# PIC18LF26K22.net
KiCad netlist of a schematic drawn in EAGLE
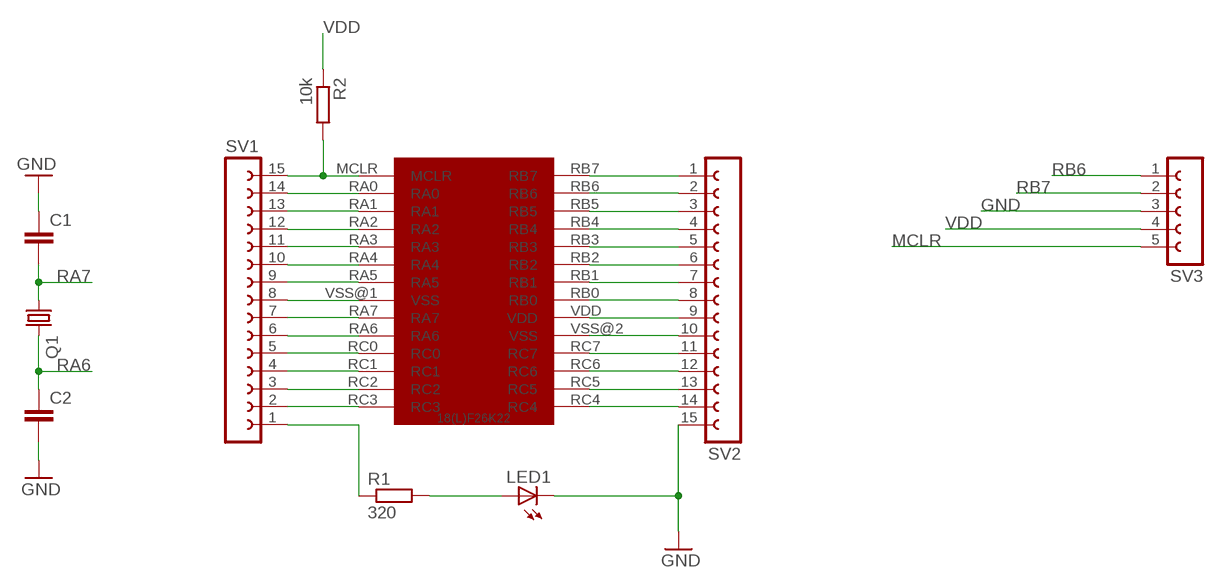
[diagram p0: schematic, sheet 1]

(export (version "E")
  (design (tool "Eeschema 10.0.6"))
  (components
    (comp (ref "C1")
      (value "C-EU025-024X044")
      (footprint "eagle-import:C025-024X044")
      (libsource (lib "eagle-import") (part "C-EU025-024X044"))
    )
    (comp (ref "C2")
      (value "C-EU025-024X044")
      (footprint "eagle-import:C025-024X044")
      (libsource (lib "eagle-import") (part "C-EU025-024X044"))
    )
    (comp (ref "LED1")
      (value "LED5MM")
      (footprint "eagle-import:LED5MM")
      (libsource (lib "eagle-import") (part "LED5MM"))
    )
    (comp (ref "Q1")
      (value "CRYSTALHC49S")
      (footprint "eagle-import:HC49_S")
      (libsource (lib "eagle-import") (part "CRYSTALHC49S"))
    )
    (comp (ref "R1")
      (value "320")
      (footprint "eagle-import:0207_10")
      (libsource (lib "eagle-import") (part "R-EU_0207/10"))
    )
    (comp (ref "R2")
      (value "10k")
      (footprint "eagle-import:0207_10")
      (libsource (lib "eagle-import") (part "R-EU_0207/10"))
    )
    (comp (ref "SV1")
      (value "FE15-1")
      (footprint "eagle-import:FE15")
      (libsource (lib "eagle-import") (part "FE15-1"))
    )
    (comp (ref "SV2")
      (value "FE15-1")
      (footprint "eagle-import:FE15")
      (libsource (lib "eagle-import") (part "FE15-1"))
    )
    (comp (ref "SV3")
      (value "FE05-1")
      (footprint "eagle-import:FE05-1")
      (libsource (lib "eagle-import") (part "FE05-1"))
    )
    (comp (ref "U$1")
      (value "PIC18(L)F26K22")
      (footprint "eagle-import:28-LEAD_SOIC")
      (libsource (lib "eagle-import") (part "PIC18(L)F26K22"))
    )
  )
  (nets
    (net (code "1") (name "/MCLR") (class "Default")
      (node (ref "R2") (pin "2") (pinfunction "2_2") (pintype "passive"))
      (node (ref "SV1") (pin "15") (pinfunction "15_15") (pintype "passive"))
      (node (ref "SV3") (pin "5") (pinfunction "5_5") (pintype "passive"))
      (node (ref "U$1") (pin "MCLR") (pinfunction "MCLR_MCLR") (pintype "bidirectional"))
    )
    (net (code "2") (name "/RA6") (class "Default")
      (node (ref "C2") (pin "1") (pinfunction "1_1") (pintype "passive"))
      (node (ref "Q1") (pin "2") (pinfunction "2_2") (pintype "passive"))
      (node (ref "SV1") (pin "6") (pinfunction "6_6") (pintype "passive"))
      (node (ref "U$1") (pin "RA6") (pinfunction "RA6_RA6") (pintype "bidirectional"))
    )
    (net (code "3") (name "/RA7") (class "Default")
      (node (ref "C1") (pin "2") (pinfunction "2_2") (pintype "passive"))
      (node (ref "Q1") (pin "1") (pinfunction "1_1") (pintype "passive"))
      (node (ref "SV1") (pin "7") (pinfunction "7_7") (pintype "passive"))
      (node (ref "U$1") (pin "RA7") (pinfunction "RA7_RA7") (pintype "bidirectional"))
    )
    (net (code "4") (name "/RB6") (class "Default")
      (node (ref "SV2") (pin "2") (pinfunction "2_2") (pintype "passive"))
      (node (ref "SV3") (pin "1") (pinfunction "1_1") (pintype "passive"))
      (node (ref "U$1") (pin "RB6") (pinfunction "RB6_RB6") (pintype "bidirectional"))
    )
    (net (code "5") (name "/RB7") (class "Default")
      (node (ref "SV2") (pin "1") (pinfunction "1_1") (pintype "passive"))
      (node (ref "SV3") (pin "2") (pinfunction "2_2") (pintype "passive"))
      (node (ref "U$1") (pin "RB7") (pinfunction "RB7_RB7") (pintype "bidirectional"))
    )
    (net (code "6") (name "/VDD") (class "Default")
      (node (ref "R2") (pin "1") (pinfunction "1_1") (pintype "passive"))
      (node (ref "SV2") (pin "9") (pinfunction "9_9") (pintype "passive"))
      (node (ref "SV3") (pin "4") (pinfunction "4_4") (pintype "passive"))
      (node (ref "U$1") (pin "VDD") (pinfunction "VDD_VDD") (pintype "bidirectional"))
    )
    (net (code "7") (name "GND") (class "Default")
      (node (ref "C1") (pin "1") (pinfunction "1_1") (pintype "passive"))
      (node (ref "C2") (pin "2") (pinfunction "2_2") (pintype "passive"))
      (node (ref "LED1") (pin "K") (pinfunction "C_K") (pintype "passive"))
      (node (ref "SV1") (pin "8") (pinfunction "8_8") (pintype "passive"))
      (node (ref "SV2") (pin "10") (pinfunction "10_10") (pintype "passive"))
      (node (ref "SV2") (pin "15") (pinfunction "15_15") (pintype "passive"))
      (node (ref "SV3") (pin "3") (pinfunction "3_3") (pintype "passive"))
      (node (ref "U$1") (pin "VSS@1") (pinfunction "VSS_VSS@1") (pintype "bidirectional"))
      (node (ref "U$1") (pin "VSS@2") (pinfunction "VSS_VSS@2") (pintype "bidirectional"))
    )
    (net (code "8") (name "Net-(LED1-PadA)") (class "Default")
      (node (ref "LED1") (pin "A") (pinfunction "A_A") (pintype "passive"))
      (node (ref "R1") (pin "2") (pinfunction "2_2") (pintype "passive"))
    )
    (net (code "9") (name "Net-(R1-Pad1)") (class "Default")
      (node (ref "R1") (pin "1") (pinfunction "1_1") (pintype "passive"))
      (node (ref "SV1") (pin "1") (pinfunction "1_1") (pintype "passive"))
    )
    (net (code "10") (name "Net-(SV1-Pad2)") (class "Default")
      (node (ref "SV1") (pin "2") (pinfunction "2_2") (pintype "passive"))
      (node (ref "U$1") (pin "RC3") (pinfunction "RC3_RC3") (pintype "bidirectional"))
    )
    (net (code "11") (name "Net-(SV1-Pad3)") (class "Default")
      (node (ref "SV1") (pin "3") (pinfunction "3_3") (pintype "passive"))
      (node (ref "U$1") (pin "RC2") (pinfunction "RC2_RC2") (pintype "bidirectional"))
    )
    (net (code "12") (name "Net-(SV1-Pad4)") (class "Default")
      (node (ref "SV1") (pin "4") (pinfunction "4_4") (pintype "passive"))
      (node (ref "U$1") (pin "RC1") (pinfunction "RC1_RC1") (pintype "bidirectional"))
    )
    (net (code "13") (name "Net-(SV1-Pad5)") (class "Default")
      (node (ref "SV1") (pin "5") (pinfunction "5_5") (pintype "passive"))
      (node (ref "U$1") (pin "RC0") (pinfunction "RC0_RC0") (pintype "bidirectional"))
    )
    (net (code "14") (name "Net-(SV1-Pad9)") (class "Default")
      (node (ref "SV1") (pin "9") (pinfunction "9_9") (pintype "passive"))
      (node (ref "U$1") (pin "RA5") (pinfunction "RA5_RA5") (pintype "bidirectional"))
    )
    (net (code "15") (name "Net-(SV1-Pad10)") (class "Default")
      (node (ref "SV1") (pin "10") (pinfunction "10_10") (pintype "passive"))
      (node (ref "U$1") (pin "RA4") (pinfunction "RA4_RA4") (pintype "bidirectional"))
    )
    (net (code "16") (name "Net-(SV1-Pad11)") (class "Default")
      (node (ref "SV1") (pin "11") (pinfunction "11_11") (pintype "passive"))
      (node (ref "U$1") (pin "RA3") (pinfunction "RA3_RA3") (pintype "bidirectional"))
    )
    (net (code "17") (name "Net-(SV1-Pad12)") (class "Default")
      (node (ref "SV1") (pin "12") (pinfunction "12_12") (pintype "passive"))
      (node (ref "U$1") (pin "RA2") (pinfunction "RA2_RA2") (pintype "bidirectional"))
    )
    (net (code "18") (name "Net-(SV1-Pad13)") (class "Default")
      (node (ref "SV1") (pin "13") (pinfunction "13_13") (pintype "passive"))
      (node (ref "U$1") (pin "RA1") (pinfunction "RA1_RA1") (pintype "bidirectional"))
    )
    (net (code "19") (name "Net-(SV1-Pad14)") (class "Default")
      (node (ref "SV1") (pin "14") (pinfunction "14_14") (pintype "passive"))
      (node (ref "U$1") (pin "RA0") (pinfunction "RA0_RA0") (pintype "bidirectional"))
    )
    (net (code "20") (name "Net-(SV2-Pad3)") (class "Default")
      (node (ref "SV2") (pin "3") (pinfunction "3_3") (pintype "passive"))
      (node (ref "U$1") (pin "RB5") (pinfunction "RB5_RB5") (pintype "bidirectional"))
    )
    (net (code "21") (name "Net-(SV2-Pad4)") (class "Default")
      (node (ref "SV2") (pin "4") (pinfunction "4_4") (pintype "passive"))
      (node (ref "U$1") (pin "RB4") (pinfunction "RB4_RB4") (pintype "bidirectional"))
    )
    (net (code "22") (name "Net-(SV2-Pad5)") (class "Default")
      (node (ref "SV2") (pin "5") (pinfunction "5_5") (pintype "passive"))
      (node (ref "U$1") (pin "RB3") (pinfunction "RB3_RB3") (pintype "bidirectional"))
    )
    (net (code "23") (name "Net-(SV2-Pad6)") (class "Default")
      (node (ref "SV2") (pin "6") (pinfunction "6_6") (pintype "passive"))
      (node (ref "U$1") (pin "RB2") (pinfunction "RB2_RB2") (pintype "bidirectional"))
    )
    (net (code "24") (name "Net-(SV2-Pad7)") (class "Default")
      (node (ref "SV2") (pin "7") (pinfunction "7_7") (pintype "passive"))
      (node (ref "U$1") (pin "RB1") (pinfunction "RB1_RB1") (pintype "bidirectional"))
    )
    (net (code "25") (name "Net-(SV2-Pad8)") (class "Default")
      (node (ref "SV2") (pin "8") (pinfunction "8_8") (pintype "passive"))
      (node (ref "U$1") (pin "RB0") (pinfunction "RB0_RB0") (pintype "bidirectional"))
    )
    (net (code "26") (name "Net-(SV2-Pad11)") (class "Default")
      (node (ref "SV2") (pin "11") (pinfunction "11_11") (pintype "passive"))
      (node (ref "U$1") (pin "RC7") (pinfunction "RC7_RC7") (pintype "bidirectional"))
    )
    (net (code "27") (name "Net-(SV2-Pad12)") (class "Default")
      (node (ref "SV2") (pin "12") (pinfunction "12_12") (pintype "passive"))
      (node (ref "U$1") (pin "RC6") (pinfunction "RC6_RC6") (pintype "bidirectional"))
    )
    (net (code "28") (name "Net-(SV2-Pad13)") (class "Default")
      (node (ref "SV2") (pin "13") (pinfunction "13_13") (pintype "passive"))
      (node (ref "U$1") (pin "RC5") (pinfunction "RC5_RC5") (pintype "bidirectional"))
    )
    (net (code "29") (name "Net-(SV2-Pad14)") (class "Default")
      (node (ref "SV2") (pin "14") (pinfunction "14_14") (pintype "passive"))
      (node (ref "U$1") (pin "RC4") (pinfunction "RC4_RC4") (pintype "bidirectional"))
    )
  )
)
